# Sheet1.net
KiCad netlist of a schematic drawn in Altium Designer
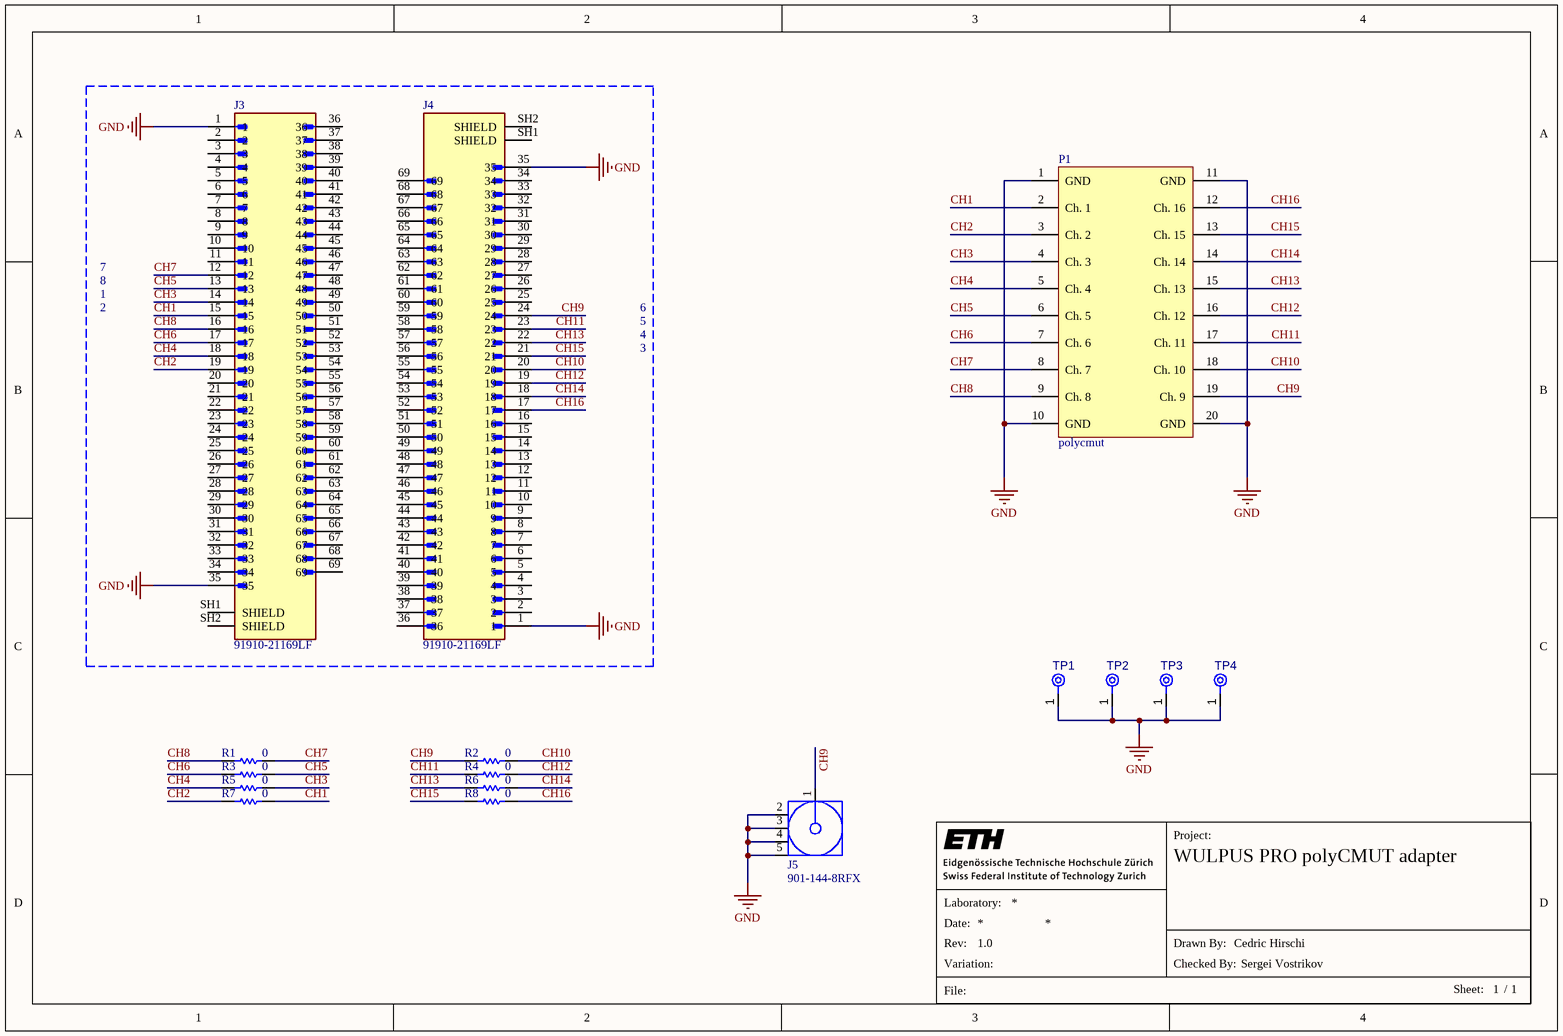
[diagram p0: Sheet1.SchDoc]

(export (version "E")
  (design (tool "Eeschema 10.0.6"))
  (components
    (comp (ref "J3")
      (value "91910-21169LF")
      (footprint "AMPHENOL_91910-21169LF")
      (fields (field (name "MF") "Amphenol ICC (FCI)"))
      (libsource (lib "91910-21169LF") (part "91910-21169LF"))
    )
    (comp (ref "J4")
      (value "91910-21169LF")
      (footprint "AMPHENOL_91910-21169LF")
      (fields (field (name "MF") "Amphenol ICC (FCI)"))
      (libsource (lib "91910-21169LF") (part "91910-21169LF"))
    )
    (comp (ref "J5")
      (value "901-144-8RFX")
      (footprint "AMPH-901-144-8RFX_V")
      (description "Coaxial Connector, 18 GHz, 50 Ohm, -65 to 165 degC, 5-Pin THD, RoHS, Bulk")
      (fields (field (name "MANUFACTURER") "Amphenol"))
      (libsource (lib "Altium Content Vault") (part "CN-S-4F-RF5"))
    )
    (comp (ref "P1")
      (value "polycmut")
      (footprint "Interposer")
      (libsource (lib "polycmut") (part "polycmut"))
    )
    (comp (ref "R1")
      (value "0")
      (footprint "RESC1005X40X25NL05T10")
      (fields (field (name "MANUFACTURER") "Yageo / Phycomp") (field (name "PART NUMBER") "RC0402JR-070RL"))
      (libsource (lib "Altium Content Vault") (part "RES"))
    )
    (comp (ref "R2")
      (value "0")
      (footprint "RESC1005X40X25NL05T10")
      (fields (field (name "MANUFACTURER") "Yageo / Phycomp") (field (name "PART NUMBER") "RC0402JR-070RL"))
      (libsource (lib "Altium Content Vault") (part "RES"))
    )
    (comp (ref "R3")
      (value "0")
      (footprint "RESC1005X40X25NL05T10")
      (fields (field (name "MANUFACTURER") "Yageo / Phycomp") (field (name "PART NUMBER") "RC0402JR-070RL"))
      (libsource (lib "Altium Content Vault") (part "RES"))
    )
    (comp (ref "R4")
      (value "0")
      (footprint "RESC1005X40X25NL05T10")
      (fields (field (name "MANUFACTURER") "Yageo / Phycomp") (field (name "PART NUMBER") "RC0402JR-070RL"))
      (libsource (lib "Altium Content Vault") (part "RES"))
    )
    (comp (ref "R5")
      (value "0")
      (footprint "RESC1005X40X25NL05T10")
      (fields (field (name "MANUFACTURER") "Yageo / Phycomp") (field (name "PART NUMBER") "RC0402JR-070RL"))
      (libsource (lib "Altium Content Vault") (part "RES"))
    )
    (comp (ref "R6")
      (value "0")
      (footprint "RESC1005X40X25NL05T10")
      (fields (field (name "MANUFACTURER") "Yageo / Phycomp") (field (name "PART NUMBER") "RC0402JR-070RL"))
      (libsource (lib "Altium Content Vault") (part "RES"))
    )
    (comp (ref "R7")
      (value "0")
      (footprint "RESC1005X40X25NL05T10")
      (fields (field (name "MANUFACTURER") "Yageo / Phycomp") (field (name "PART NUMBER") "RC0402JR-070RL"))
      (libsource (lib "Altium Content Vault") (part "RES"))
    )
    (comp (ref "R8")
      (value "0")
      (footprint "RESC1005X40X25NL05T10")
      (fields (field (name "MANUFACTURER") "Yageo / Phycomp") (field (name "PART NUMBER") "RC0402JR-070RL"))
      (libsource (lib "Altium Content Vault") (part "RES"))
    )
    (comp (ref "TP1")
      (value "TPAD6R")
      (footprint "TP06R")
      (description "0.6mm round")
      (libsource (lib "Cédric's Workspace") (part "CMP-001-0001-4"))
    )
    (comp (ref "TP2")
      (value "TPAD6R")
      (footprint "TP06R")
      (description "0.6mm round")
      (libsource (lib "Cédric's Workspace") (part "CMP-001-0001-4"))
    )
    (comp (ref "TP3")
      (value "TPAD6R")
      (footprint "TP06R")
      (description "0.6mm round")
      (libsource (lib "Cédric's Workspace") (part "CMP-001-0001-4"))
    )
    (comp (ref "TP4")
      (value "TPAD6R")
      (footprint "TP06R")
      (description "0.6mm round")
      (libsource (lib "Cédric's Workspace") (part "CMP-001-0001-4"))
    )
  )
  (nets
    (net (code "1") (name "/CH1") (class "Default")
      (node (ref "J3") (pin "15") (pinfunction "15_15") (pintype "passive"))
      (node (ref "P1") (pin "2") (pinfunction "Ch._1_2") (pintype "passive"))
      (node (ref "R7") (pin "2") (pinfunction "2_2") (pintype "passive"))
    )
    (net (code "2") (name "/CH2") (class "Default")
      (node (ref "J3") (pin "19") (pinfunction "19_19") (pintype "passive"))
      (node (ref "P1") (pin "3") (pinfunction "Ch._2_3") (pintype "passive"))
      (node (ref "R7") (pin "1") (pinfunction "1_1") (pintype "passive"))
    )
    (net (code "3") (name "/CH3") (class "Default")
      (node (ref "J3") (pin "14") (pinfunction "14_14") (pintype "passive"))
      (node (ref "P1") (pin "4") (pinfunction "Ch._3_4") (pintype "passive"))
      (node (ref "R5") (pin "2") (pinfunction "2_2") (pintype "passive"))
    )
    (net (code "4") (name "/CH4") (class "Default")
      (node (ref "J3") (pin "18") (pinfunction "18_18") (pintype "passive"))
      (node (ref "P1") (pin "5") (pinfunction "Ch._4_5") (pintype "passive"))
      (node (ref "R5") (pin "1") (pinfunction "1_1") (pintype "passive"))
    )
    (net (code "5") (name "/CH5") (class "Default")
      (node (ref "J3") (pin "13") (pinfunction "13_13") (pintype "passive"))
      (node (ref "P1") (pin "6") (pinfunction "Ch._5_6") (pintype "passive"))
      (node (ref "R3") (pin "2") (pinfunction "2_2") (pintype "passive"))
    )
    (net (code "6") (name "/CH6") (class "Default")
      (node (ref "J3") (pin "17") (pinfunction "17_17") (pintype "passive"))
      (node (ref "P1") (pin "7") (pinfunction "Ch._6_7") (pintype "passive"))
      (node (ref "R3") (pin "1") (pinfunction "1_1") (pintype "passive"))
    )
    (net (code "7") (name "/CH7") (class "Default")
      (node (ref "J3") (pin "12") (pinfunction "12_12") (pintype "passive"))
      (node (ref "P1") (pin "8") (pinfunction "Ch._7_8") (pintype "passive"))
      (node (ref "R1") (pin "2") (pinfunction "2_2") (pintype "passive"))
    )
    (net (code "8") (name "/CH8") (class "Default")
      (node (ref "J3") (pin "16") (pinfunction "16_16") (pintype "passive"))
      (node (ref "P1") (pin "9") (pinfunction "Ch._8_9") (pintype "passive"))
      (node (ref "R1") (pin "1") (pinfunction "1_1") (pintype "passive"))
    )
    (net (code "9") (name "/CH9") (class "Default")
      (node (ref "J4") (pin "24") (pinfunction "24_24") (pintype "passive"))
      (node (ref "J5") (pin "1") (pinfunction "1_1") (pintype "passive"))
      (node (ref "P1") (pin "19") (pinfunction "Ch._9_19") (pintype "passive"))
      (node (ref "R2") (pin "1") (pinfunction "1_1") (pintype "passive"))
    )
    (net (code "10") (name "/CH10") (class "Default")
      (node (ref "J4") (pin "20") (pinfunction "20_20") (pintype "passive"))
      (node (ref "P1") (pin "18") (pinfunction "Ch._10_18") (pintype "passive"))
      (node (ref "R2") (pin "2") (pinfunction "2_2") (pintype "passive"))
    )
    (net (code "11") (name "/CH11") (class "Default")
      (node (ref "J4") (pin "23") (pinfunction "23_23") (pintype "passive"))
      (node (ref "P1") (pin "17") (pinfunction "Ch._11_17") (pintype "passive"))
      (node (ref "R4") (pin "1") (pinfunction "1_1") (pintype "passive"))
    )
    (net (code "12") (name "/CH12") (class "Default")
      (node (ref "J4") (pin "19") (pinfunction "19_19") (pintype "passive"))
      (node (ref "P1") (pin "16") (pinfunction "Ch._12_16") (pintype "passive"))
      (node (ref "R4") (pin "2") (pinfunction "2_2") (pintype "passive"))
    )
    (net (code "13") (name "/CH13") (class "Default")
      (node (ref "J4") (pin "22") (pinfunction "22_22") (pintype "passive"))
      (node (ref "P1") (pin "15") (pinfunction "Ch._13_15") (pintype "passive"))
      (node (ref "R6") (pin "1") (pinfunction "1_1") (pintype "passive"))
    )
    (net (code "14") (name "/CH14") (class "Default")
      (node (ref "J4") (pin "18") (pinfunction "18_18") (pintype "passive"))
      (node (ref "P1") (pin "14") (pinfunction "Ch._14_14") (pintype "passive"))
      (node (ref "R6") (pin "2") (pinfunction "2_2") (pintype "passive"))
    )
    (net (code "15") (name "/CH15") (class "Default")
      (node (ref "J4") (pin "21") (pinfunction "21_21") (pintype "passive"))
      (node (ref "P1") (pin "13") (pinfunction "Ch._15_13") (pintype "passive"))
      (node (ref "R8") (pin "1") (pinfunction "1_1") (pintype "passive"))
    )
    (net (code "16") (name "/CH16") (class "Default")
      (node (ref "J4") (pin "17") (pinfunction "17_17") (pintype "passive"))
      (node (ref "P1") (pin "12") (pinfunction "Ch._16_12") (pintype "passive"))
      (node (ref "R8") (pin "2") (pinfunction "2_2") (pintype "passive"))
    )
    (net (code "17") (name "GND") (class "Default")
      (node (ref "J3") (pin "1") (pinfunction "1_1") (pintype "passive"))
      (node (ref "J3") (pin "35") (pinfunction "35_35") (pintype "passive"))
      (node (ref "J4") (pin "1") (pinfunction "1_1") (pintype "passive"))
      (node (ref "J4") (pin "35") (pinfunction "35_35") (pintype "passive"))
      (node (ref "J5") (pin "2") (pinfunction "2_2") (pintype "passive"))
      (node (ref "J5") (pin "3") (pinfunction "3_3") (pintype "passive"))
      (node (ref "J5") (pin "4") (pinfunction "4_4") (pintype "passive"))
      (node (ref "J5") (pin "5") (pinfunction "5_5") (pintype "passive"))
      (node (ref "P1") (pin "1") (pinfunction "GND_1") (pintype "passive"))
      (node (ref "P1") (pin "10") (pinfunction "GND_10") (pintype "passive"))
      (node (ref "P1") (pin "11") (pinfunction "GND_11") (pintype "passive"))
      (node (ref "P1") (pin "20") (pinfunction "GND_20") (pintype "passive"))
      (node (ref "TP1") (pin "1") (pinfunction "TP_1") (pintype "passive"))
      (node (ref "TP2") (pin "1") (pinfunction "TP_1") (pintype "passive"))
      (node (ref "TP3") (pin "1") (pinfunction "TP_1") (pintype "passive"))
      (node (ref "TP4") (pin "1") (pinfunction "TP_1") (pintype "passive"))
    )
    (net (code "18") (name "unconnected-(J3-Pad2)") (class "Default")
      (node (ref "J3") (pin "2") (pinfunction "2_2") (pintype "passive"))
    )
    (net (code "19") (name "unconnected-(J3-Pad3)") (class "Default")
      (node (ref "J3") (pin "3") (pinfunction "3_3") (pintype "passive"))
    )
    (net (code "20") (name "unconnected-(J3-Pad4)") (class "Default")
      (node (ref "J3") (pin "4") (pinfunction "4_4") (pintype "passive"))
    )
    (net (code "21") (name "unconnected-(J3-Pad5)") (class "Default")
      (node (ref "J3") (pin "5") (pinfunction "5_5") (pintype "passive"))
    )
    (net (code "22") (name "unconnected-(J3-Pad6)") (class "Default")
      (node (ref "J3") (pin "6") (pinfunction "6_6") (pintype "passive"))
    )
    (net (code "23") (name "unconnected-(J3-Pad7)") (class "Default")
      (node (ref "J3") (pin "7") (pinfunction "7_7") (pintype "passive"))
    )
    (net (code "24") (name "unconnected-(J3-Pad8)") (class "Default")
      (node (ref "J3") (pin "8") (pinfunction "8_8") (pintype "passive"))
    )
    (net (code "25") (name "unconnected-(J3-Pad9)") (class "Default")
      (node (ref "J3") (pin "9") (pinfunction "9_9") (pintype "passive"))
    )
    (net (code "26") (name "unconnected-(J3-Pad10)") (class "Default")
      (node (ref "J3") (pin "10") (pinfunction "10_10") (pintype "passive"))
    )
    (net (code "27") (name "unconnected-(J3-Pad11)") (class "Default")
      (node (ref "J3") (pin "11") (pinfunction "11_11") (pintype "passive"))
    )
    (net (code "28") (name "unconnected-(J3-Pad20)") (class "Default")
      (node (ref "J3") (pin "20") (pinfunction "20_20") (pintype "passive"))
    )
    (net (code "29") (name "unconnected-(J3-Pad21)") (class "Default")
      (node (ref "J3") (pin "21") (pinfunction "21_21") (pintype "passive"))
    )
    (net (code "30") (name "unconnected-(J3-Pad22)") (class "Default")
      (node (ref "J3") (pin "22") (pinfunction "22_22") (pintype "passive"))
    )
    (net (code "31") (name "unconnected-(J3-Pad23)") (class "Default")
      (node (ref "J3") (pin "23") (pinfunction "23_23") (pintype "passive"))
    )
    (net (code "32") (name "unconnected-(J3-Pad24)") (class "Default")
      (node (ref "J3") (pin "24") (pinfunction "24_24") (pintype "passive"))
    )
    (net (code "33") (name "unconnected-(J3-Pad25)") (class "Default")
      (node (ref "J3") (pin "25") (pinfunction "25_25") (pintype "passive"))
    )
    (net (code "34") (name "unconnected-(J3-Pad26)") (class "Default")
      (node (ref "J3") (pin "26") (pinfunction "26_26") (pintype "passive"))
    )
    (net (code "35") (name "unconnected-(J3-Pad27)") (class "Default")
      (node (ref "J3") (pin "27") (pinfunction "27_27") (pintype "passive"))
    )
    (net (code "36") (name "unconnected-(J3-Pad28)") (class "Default")
      (node (ref "J3") (pin "28") (pinfunction "28_28") (pintype "passive"))
    )
    (net (code "37") (name "unconnected-(J3-Pad29)") (class "Default")
      (node (ref "J3") (pin "29") (pinfunction "29_29") (pintype "passive"))
    )
    (net (code "38") (name "unconnected-(J3-Pad30)") (class "Default")
      (node (ref "J3") (pin "30") (pinfunction "30_30") (pintype "passive"))
    )
    (net (code "39") (name "unconnected-(J3-Pad31)") (class "Default")
      (node (ref "J3") (pin "31") (pinfunction "31_31") (pintype "passive"))
    )
    (net (code "40") (name "unconnected-(J3-Pad32)") (class "Default")
      (node (ref "J3") (pin "32") (pinfunction "32_32") (pintype "passive"))
    )
    (net (code "41") (name "unconnected-(J3-Pad33)") (class "Default")
      (node (ref "J3") (pin "33") (pinfunction "33_33") (pintype "passive"))
    )
    (net (code "42") (name "unconnected-(J3-Pad34)") (class "Default")
      (node (ref "J3") (pin "34") (pinfunction "34_34") (pintype "passive"))
    )
    (net (code "43") (name "unconnected-(J3-Pad36)") (class "Default")
      (node (ref "J3") (pin "36") (pinfunction "36_36") (pintype "passive"))
    )
    (net (code "44") (name "unconnected-(J3-Pad37)") (class "Default")
      (node (ref "J3") (pin "37") (pinfunction "37_37") (pintype "passive"))
    )
    (net (code "45") (name "unconnected-(J3-Pad38)") (class "Default")
      (node (ref "J3") (pin "38") (pinfunction "38_38") (pintype "passive"))
    )
    (net (code "46") (name "unconnected-(J3-Pad39)") (class "Default")
      (node (ref "J3") (pin "39") (pinfunction "39_39") (pintype "passive"))
    )
    (net (code "47") (name "unconnected-(J3-Pad40)") (class "Default")
      (node (ref "J3") (pin "40") (pinfunction "40_40") (pintype "passive"))
    )
    (net (code "48") (name "unconnected-(J3-Pad41)") (class "Default")
      (node (ref "J3") (pin "41") (pinfunction "41_41") (pintype "passive"))
    )
    (net (code "49") (name "unconnected-(J3-Pad42)") (class "Default")
      (node (ref "J3") (pin "42") (pinfunction "42_42") (pintype "passive"))
    )
    (net (code "50") (name "unconnected-(J3-Pad43)") (class "Default")
      (node (ref "J3") (pin "43") (pinfunction "43_43") (pintype "passive"))
    )
    (net (code "51") (name "unconnected-(J3-Pad44)") (class "Default")
      (node (ref "J3") (pin "44") (pinfunction "44_44") (pintype "passive"))
    )
    (net (code "52") (name "unconnected-(J3-Pad45)") (class "Default")
      (node (ref "J3") (pin "45") (pinfunction "45_45") (pintype "passive"))
    )
    (net (code "53") (name "unconnected-(J3-Pad46)") (class "Default")
      (node (ref "J3") (pin "46") (pinfunction "46_46") (pintype "passive"))
    )
    (net (code "54") (name "unconnected-(J3-Pad47)") (class "Default")
      (node (ref "J3") (pin "47") (pinfunction "47_47") (pintype "passive"))
    )
    (net (code "55") (name "unconnected-(J3-Pad48)") (class "Default")
      (node (ref "J3") (pin "48") (pinfunction "48_48") (pintype "passive"))
    )
    (net (code "56") (name "unconnected-(J3-Pad49)") (class "Default")
      (node (ref "J3") (pin "49") (pinfunction "49_49") (pintype "passive"))
    )
    (net (code "57") (name "unconnected-(J3-Pad50)") (class "Default")
      (node (ref "J3") (pin "50") (pinfunction "50_50") (pintype "passive"))
    )
    (net (code "58") (name "unconnected-(J3-Pad51)") (class "Default")
      (node (ref "J3") (pin "51") (pinfunction "51_51") (pintype "passive"))
    )
    (net (code "59") (name "unconnected-(J3-Pad52)") (class "Default")
      (node (ref "J3") (pin "52") (pinfunction "52_52") (pintype "passive"))
    )
    (net (code "60") (name "unconnected-(J3-Pad53)") (class "Default")
      (node (ref "J3") (pin "53") (pinfunction "53_53") (pintype "passive"))
    )
    (net (code "61") (name "unconnected-(J3-Pad54)") (class "Default")
      (node (ref "J3") (pin "54") (pinfunction "54_54") (pintype "passive"))
    )
    (net (code "62") (name "unconnected-(J3-Pad55)") (class "Default")
      (node (ref "J3") (pin "55") (pinfunction "55_55") (pintype "passive"))
    )
    (net (code "63") (name "unconnected-(J3-Pad56)") (class "Default")
      (node (ref "J3") (pin "56") (pinfunction "56_56") (pintype "passive"))
    )
    (net (code "64") (name "unconnected-(J3-Pad57)") (class "Default")
      (node (ref "J3") (pin "57") (pinfunction "57_57") (pintype "passive"))
    )
    (net (code "65") (name "unconnected-(J3-Pad58)") (class "Default")
      (node (ref "J3") (pin "58") (pinfunction "58_58") (pintype "passive"))
    )
    (net (code "66") (name "unconnected-(J3-Pad59)") (class "Default")
      (node (ref "J3") (pin "59") (pinfunction "59_59") (pintype "passive"))
    )
    (net (code "67") (name "unconnected-(J3-Pad60)") (class "Default")
      (node (ref "J3") (pin "60") (pinfunction "60_60") (pintype "passive"))
    )
    (net (code "68") (name "unconnected-(J3-Pad61)") (class "Default")
      (node (ref "J3") (pin "61") (pinfunction "61_61") (pintype "passive"))
    )
    (net (code "69") (name "unconnected-(J3-Pad62)") (class "Default")
      (node (ref "J3") (pin "62") (pinfunction "62_62") (pintype "passive"))
    )
    (net (code "70") (name "unconnected-(J3-Pad63)") (class "Default")
      (node (ref "J3") (pin "63") (pinfunction "63_63") (pintype "passive"))
    )
    (net (code "71") (name "unconnected-(J3-Pad64)") (class "Default")
      (node (ref "J3") (pin "64") (pinfunction "64_64") (pintype "passive"))
    )
    (net (code "72") (name "unconnected-(J3-Pad65)") (class "Default")
      (node (ref "J3") (pin "65") (pinfunction "65_65") (pintype "passive"))
    )
    (net (code "73") (name "unconnected-(J3-Pad66)") (class "Default")
      (node (ref "J3") (pin "66") (pinfunction "66_66") (pintype "passive"))
    )
    (net (code "74") (name "unconnected-(J3-Pad67)") (class "Default")
      (node (ref "J3") (pin "67") (pinfunction "67_67") (pintype "passive"))
    )
    (net (code "75") (name "unconnected-(J3-Pad68)") (class "Default")
      (node (ref "J3") (pin "68") (pinfunction "68_68") (pintype "passive"))
    )
    (net (code "76") (name "unconnected-(J3-Pad69)") (class "Default")
      (node (ref "J3") (pin "69") (pinfunction "69_69") (pintype "passive"))
    )
    (net (code "77") (name "unconnected-(J3-SHIELD-PadSH1)") (class "Default")
      (node (ref "J3") (pin "SH1") (pinfunction "SHIELD_SH1") (pintype "passive"))
    )
    (net (code "78") (name "unconnected-(J3-SHIELD-PadSH2)") (class "Default")
      (node (ref "J3") (pin "SH2") (pinfunction "SHIELD_SH2") (pintype "passive"))
    )
    (net (code "79") (name "unconnected-(J4-Pad2)") (class "Default")
      (node (ref "J4") (pin "2") (pinfunction "2_2") (pintype "passive"))
    )
    (net (code "80") (name "unconnected-(J4-Pad3)") (class "Default")
      (node (ref "J4") (pin "3") (pinfunction "3_3") (pintype "passive"))
    )
    (net (code "81") (name "unconnected-(J4-Pad4)") (class "Default")
      (node (ref "J4") (pin "4") (pinfunction "4_4") (pintype "passive"))
    )
    (net (code "82") (name "unconnected-(J4-Pad5)") (class "Default")
      (node (ref "J4") (pin "5") (pinfunction "5_5") (pintype "passive"))
    )
    (net (code "83") (name "unconnected-(J4-Pad6)") (class "Default")
      (node (ref "J4") (pin "6") (pinfunction "6_6") (pintype "passive"))
    )
    (net (code "84") (name "unconnected-(J4-Pad7)") (class "Default")
      (node (ref "J4") (pin "7") (pinfunction "7_7") (pintype "passive"))
    )
    (net (code "85") (name "unconnected-(J4-Pad8)") (class "Default")
      (node (ref "J4") (pin "8") (pinfunction "8_8") (pintype "passive"))
    )
    (net (code "86") (name "unconnected-(J4-Pad9)") (class "Default")
      (node (ref "J4") (pin "9") (pinfunction "9_9") (pintype "passive"))
    )
    (net (code "87") (name "unconnected-(J4-Pad10)") (class "Default")
      (node (ref "J4") (pin "10") (pinfunction "10_10") (pintype "passive"))
    )
    (net (code "88") (name "unconnected-(J4-Pad11)") (class "Default")
      (node (ref "J4") (pin "11") (pinfunction "11_11") (pintype "passive"))
    )
    (net (code "89") (name "unconnected-(J4-Pad12)") (class "Default")
      (node (ref "J4") (pin "12") (pinfunction "12_12") (pintype "passive"))
    )
    (net (code "90") (name "unconnected-(J4-Pad13)") (class "Default")
      (node (ref "J4") (pin "13") (pinfunction "13_13") (pintype "passive"))
    )
    (net (code "91") (name "unconnected-(J4-Pad14)") (class "Default")
      (node (ref "J4") (pin "14") (pinfunction "14_14") (pintype "passive"))
    )
    (net (code "92") (name "unconnected-(J4-Pad15)") (class "Default")
      (node (ref "J4") (pin "15") (pinfunction "15_15") (pintype "passive"))
    )
    (net (code "93") (name "unconnected-(J4-Pad16)") (class "Default")
      (node (ref "J4") (pin "16") (pinfunction "16_16") (pintype "passive"))
    )
    (net (code "94") (name "unconnected-(J4-Pad25)") (class "Default")
      (node (ref "J4") (pin "25") (pinfunction "25_25") (pintype "passive"))
    )
    (net (code "95") (name "unconnected-(J4-Pad26)") (class "Default")
      (node (ref "J4") (pin "26") (pinfunction "26_26") (pintype "passive"))
    )
    (net (code "96") (name "unconnected-(J4-Pad27)") (class "Default")
      (node (ref "J4") (pin "27") (pinfunction "27_27") (pintype "passive"))
    )
    (net (code "97") (name "unconnected-(J4-Pad28)") (class "Default")
      (node (ref "J4") (pin "28") (pinfunction "28_28") (pintype "passive"))
    )
    (net (code "98") (name "unconnected-(J4-Pad29)") (class "Default")
      (node (ref "J4") (pin "29") (pinfunction "29_29") (pintype "passive"))
    )
    (net (code "99") (name "unconnected-(J4-Pad30)") (class "Default")
      (node (ref "J4") (pin "30") (pinfunction "30_30") (pintype "passive"))
    )
    (net (code "100") (name "unconnected-(J4-Pad31)") (class "Default")
      (node (ref "J4") (pin "31") (pinfunction "31_31") (pintype "passive"))
    )
    (net (code "101") (name "unconnected-(J4-Pad32)") (class "Default")
      (node (ref "J4") (pin "32") (pinfunction "32_32") (pintype "passive"))
    )
    (net (code "102") (name "unconnected-(J4-Pad33)") (class "Default")
      (node (ref "J4") (pin "33") (pinfunction "33_33") (pintype "passive"))
    )
    (net (code "103") (name "unconnected-(J4-Pad34)") (class "Default")
      (node (ref "J4") (pin "34") (pinfunction "34_34") (pintype "passive"))
    )
    (net (code "104") (name "unconnected-(J4-Pad36)") (class "Default")
      (node (ref "J4") (pin "36") (pinfunction "36_36") (pintype "passive"))
    )
    (net (code "105") (name "unconnected-(J4-Pad37)") (class "Default")
      (node (ref "J4") (pin "37") (pinfunction "37_37") (pintype "passive"))
    )
    (net (code "106") (name "unconnected-(J4-Pad38)") (class "Default")
      (node (ref "J4") (pin "38") (pinfunction "38_38") (pintype "passive"))
    )
    (net (code "107") (name "unconnected-(J4-Pad39)") (class "Default")
      (node (ref "J4") (pin "39") (pinfunction "39_39") (pintype "passive"))
    )
    (net (code "108") (name "unconnected-(J4-Pad40)") (class "Default")
      (node (ref "J4") (pin "40") (pinfunction "40_40") (pintype "passive"))
    )
    (net (code "109") (name "unconnected-(J4-Pad41)") (class "Default")
      (node (ref "J4") (pin "41") (pinfunction "41_41") (pintype "passive"))
    )
    (net (code "110") (name "unconnected-(J4-Pad42)") (class "Default")
      (node (ref "J4") (pin "42") (pinfunction "42_42") (pintype "passive"))
    )
    (net (code "111") (name "unconnected-(J4-Pad43)") (class "Default")
      (node (ref "J4") (pin "43") (pinfunction "43_43") (pintype "passive"))
    )
    (net (code "112") (name "unconnected-(J4-Pad44)") (class "Default")
      (node (ref "J4") (pin "44") (pinfunction "44_44") (pintype "passive"))
    )
    (net (code "113") (name "unconnected-(J4-Pad45)") (class "Default")
      (node (ref "J4") (pin "45") (pinfunction "45_45") (pintype "passive"))
    )
    (net (code "114") (name "unconnected-(J4-Pad46)") (class "Default")
      (node (ref "J4") (pin "46") (pinfunction "46_46") (pintype "passive"))
    )
    (net (code "115") (name "unconnected-(J4-Pad47)") (class "Default")
      (node (ref "J4") (pin "47") (pinfunction "47_47") (pintype "passive"))
    )
    (net (code "116") (name "unconnected-(J4-Pad48)") (class "Default")
      (node (ref "J4") (pin "48") (pinfunction "48_48") (pintype "passive"))
    )
    (net (code "117") (name "unconnected-(J4-Pad49)") (class "Default")
      (node (ref "J4") (pin "49") (pinfunction "49_49") (pintype "passive"))
    )
    (net (code "118") (name "unconnected-(J4-Pad50)") (class "Default")
      (node (ref "J4") (pin "50") (pinfunction "50_50") (pintype "passive"))
    )
    (net (code "119") (name "unconnected-(J4-Pad51)") (class "Default")
      (node (ref "J4") (pin "51") (pinfunction "51_51") (pintype "passive"))
    )
    (net (code "120") (name "unconnected-(J4-Pad52)") (class "Default")
      (node (ref "J4") (pin "52") (pinfunction "52_52") (pintype "passive"))
    )
    (net (code "121") (name "unconnected-(J4-Pad53)") (class "Default")
      (node (ref "J4") (pin "53") (pinfunction "53_53") (pintype "passive"))
    )
    (net (code "122") (name "unconnected-(J4-Pad54)") (class "Default")
      (node (ref "J4") (pin "54") (pinfunction "54_54") (pintype "passive"))
    )
    (net (code "123") (name "unconnected-(J4-Pad55)") (class "Default")
      (node (ref "J4") (pin "55") (pinfunction "55_55") (pintype "passive"))
    )
    (net (code "124") (name "unconnected-(J4-Pad56)") (class "Default")
      (node (ref "J4") (pin "56") (pinfunction "56_56") (pintype "passive"))
    )
    (net (code "125") (name "unconnected-(J4-Pad57)") (class "Default")
      (node (ref "J4") (pin "57") (pinfunction "57_57") (pintype "passive"))
    )
    (net (code "126") (name "unconnected-(J4-Pad58)") (class "Default")
      (node (ref "J4") (pin "58") (pinfunction "58_58") (pintype "passive"))
    )
    (net (code "127") (name "unconnected-(J4-Pad59)") (class "Default")
      (node (ref "J4") (pin "59") (pinfunction "59_59") (pintype "passive"))
    )
    (net (code "128") (name "unconnected-(J4-Pad60)") (class "Default")
      (node (ref "J4") (pin "60") (pinfunction "60_60") (pintype "passive"))
    )
    (net (code "129") (name "unconnected-(J4-Pad61)") (class "Default")
      (node (ref "J4") (pin "61") (pinfunction "61_61") (pintype "passive"))
    )
    (net (code "130") (name "unconnected-(J4-Pad62)") (class "Default")
      (node (ref "J4") (pin "62") (pinfunction "62_62") (pintype "passive"))
    )
    (net (code "131") (name "unconnected-(J4-Pad63)") (class "Default")
      (node (ref "J4") (pin "63") (pinfunction "63_63") (pintype "passive"))
    )
    (net (code "132") (name "unconnected-(J4-Pad64)") (class "Default")
      (node (ref "J4") (pin "64") (pinfunction "64_64") (pintype "passive"))
    )
    (net (code "133") (name "unconnected-(J4-Pad65)") (class "Default")
      (node (ref "J4") (pin "65") (pinfunction "65_65") (pintype "passive"))
    )
    (net (code "134") (name "unconnected-(J4-Pad66)") (class "Default")
      (node (ref "J4") (pin "66") (pinfunction "66_66") (pintype "passive"))
    )
    (net (code "135") (name "unconnected-(J4-Pad67)") (class "Default")
      (node (ref "J4") (pin "67") (pinfunction "67_67") (pintype "passive"))
    )
    (net (code "136") (name "unconnected-(J4-Pad68)") (class "Default")
      (node (ref "J4") (pin "68") (pinfunction "68_68") (pintype "passive"))
    )
    (net (code "137") (name "unconnected-(J4-Pad69)") (class "Default")
      (node (ref "J4") (pin "69") (pinfunction "69_69") (pintype "passive"))
    )
    (net (code "138") (name "unconnected-(J4-SHIELD-PadSH1)") (class "Default")
      (node (ref "J4") (pin "SH1") (pinfunction "SHIELD_SH1") (pintype "passive"))
    )
    (net (code "139") (name "unconnected-(J4-SHIELD-PadSH2)") (class "Default")
      (node (ref "J4") (pin "SH2") (pinfunction "SHIELD_SH2") (pintype "passive"))
    )
  )
)
